# SparkIO_Thermal_Shield_-_No_Aux_ADC.net
KiCad netlist of a schematic drawn in Altium Designer
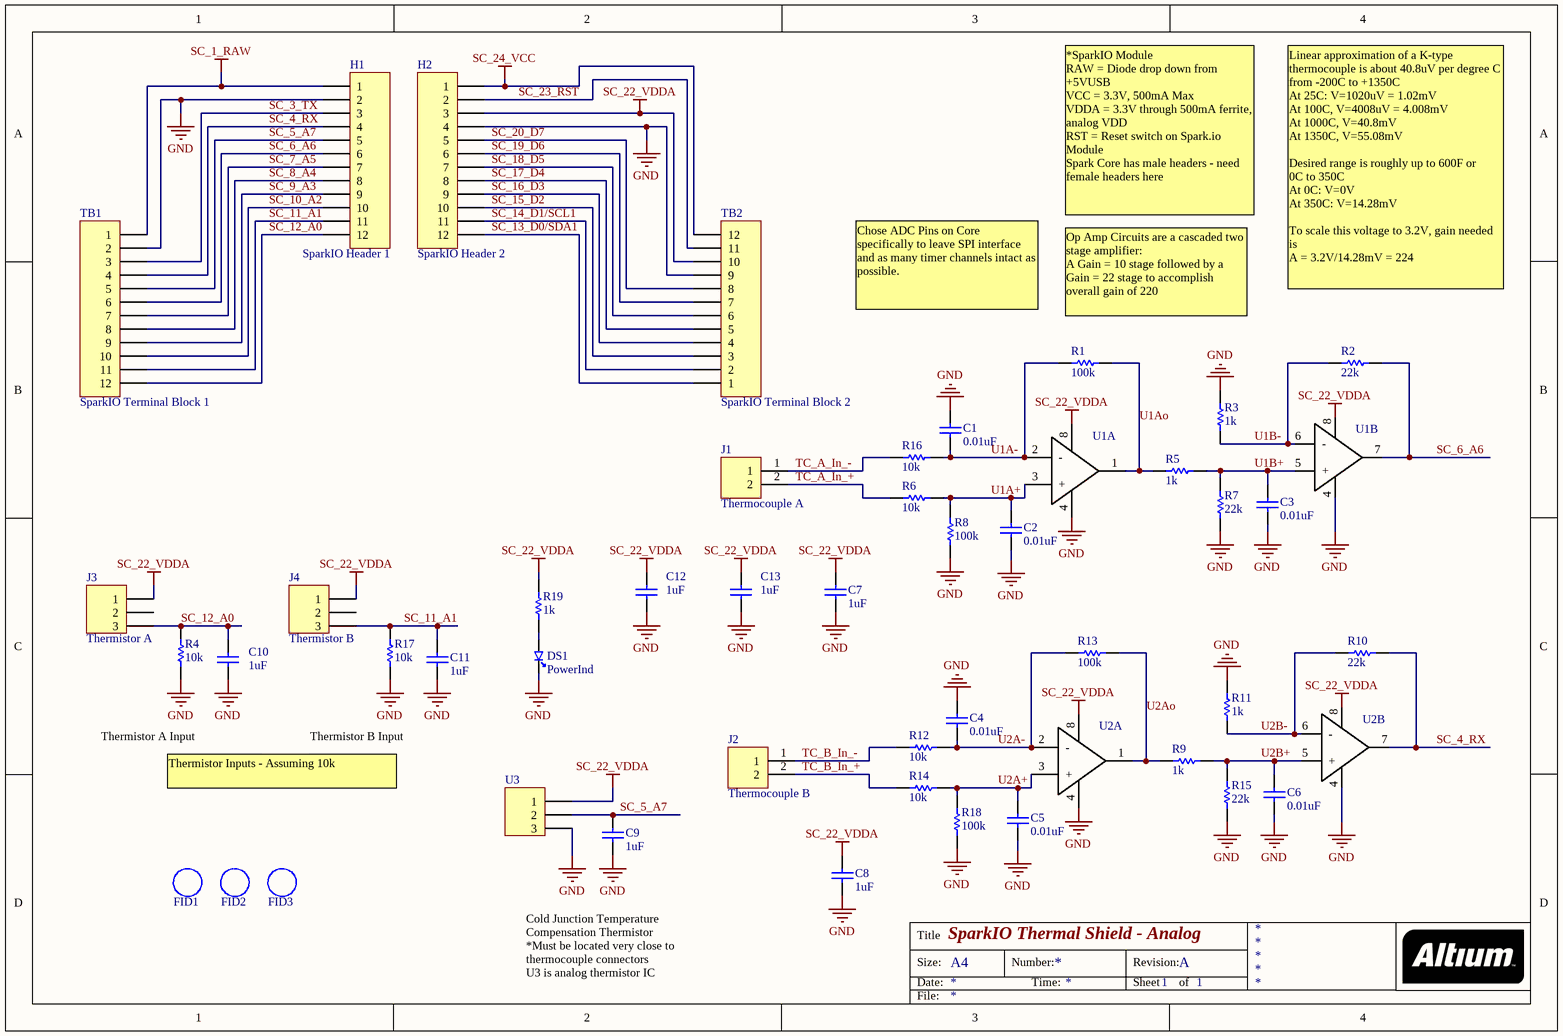
[diagram p0: SparkIO Thermal Shield - No Aux ADC.SchDoc]

(export (version "E")
  (design (tool "Eeschema 10.0.6"))
  (components
    (comp (ref "C1")
      (value "0.01uF")
      (footprint "0603 - NO SILK")
      (description "Capacitor")
      (fields
        (field (name "MANUFACTURER") "TDK Corporation")
        (field (name "MANUFACTURER PART NUMBER") "C1608X7R1E103K080AA")
      )
      (libsource (lib "MakerBot") (part "Capacitor"))
    )
    (comp (ref "C2")
      (value "0.01uF")
      (footprint "0603 - NO SILK")
      (description "Capacitor")
      (fields
        (field (name "MANUFACTURER") "TDK Corporation")
        (field (name "MANUFACTURER PART NUMBER") "C1608X7R1E103K080AA")
      )
      (libsource (lib "MakerBot") (part "Capacitor"))
    )
    (comp (ref "C3")
      (value "0.01uF")
      (footprint "0603 - NO SILK")
      (description "Capacitor")
      (fields
        (field (name "MANUFACTURER") "TDK Corporation")
        (field (name "MANUFACTURER PART NUMBER") "C1608X7R1E103K080AA")
      )
      (libsource (lib "MakerBot") (part "Capacitor"))
    )
    (comp (ref "C4")
      (value "0.01uF")
      (footprint "0603 - NO SILK")
      (description "Capacitor")
      (fields
        (field (name "MANUFACTURER") "TDK Corporation")
        (field (name "MANUFACTURER PART NUMBER") "C1608X7R1E103K080AA")
      )
      (libsource (lib "MakerBot") (part "Capacitor"))
    )
    (comp (ref "C5")
      (value "0.01uF")
      (footprint "0603 - NO SILK")
      (description "Capacitor")
      (fields
        (field (name "MANUFACTURER") "TDK Corporation")
        (field (name "MANUFACTURER PART NUMBER") "C1608X7R1E103K080AA")
      )
      (libsource (lib "MakerBot") (part "Capacitor"))
    )
    (comp (ref "C6")
      (value "0.01uF")
      (footprint "0603 - NO SILK")
      (description "Capacitor")
      (fields
        (field (name "MANUFACTURER") "TDK Corporation")
        (field (name "MANUFACTURER PART NUMBER") "C1608X7R1E103K080AA")
      )
      (libsource (lib "MakerBot") (part "Capacitor"))
    )
    (comp (ref "C7")
      (value "1uF")
      (footprint "0603 - NO SILK")
      (description "Capacitor")
      (fields
        (field (name "MANUFACTURER") "TDK Corporation")
        (field (name "MANUFACTURER PART NUMBER") "C1608X7R1C105K080AC")
      )
      (libsource (lib "MakerBot") (part "Capacitor"))
    )
    (comp (ref "C8")
      (value "1uF")
      (footprint "0603 - NO SILK")
      (description "Capacitor")
      (fields
        (field (name "MANUFACTURER") "TDK Corporation")
        (field (name "MANUFACTURER PART NUMBER") "C1608X7R1C105K080AC")
      )
      (libsource (lib "MakerBot") (part "Capacitor"))
    )
    (comp (ref "C9")
      (value "1uF")
      (footprint "0603 - NO SILK")
      (description "Capacitor")
      (fields
        (field (name "MANUFACTURER") "TDK Corporation")
        (field (name "MANUFACTURER PART NUMBER") "C1608X7R1C105K080AC")
      )
      (libsource (lib "MakerBot") (part "Capacitor"))
    )
    (comp (ref "C10")
      (value "1uF")
      (footprint "0603 - NO SILK")
      (description "Capacitor")
      (fields
        (field (name "MANUFACTURER") "TDK Corporation")
        (field (name "MANUFACTURER PART NUMBER") "C1608X7R1C105K080AC")
      )
      (libsource (lib "MakerBot") (part "Capacitor"))
    )
    (comp (ref "C11")
      (value "1uF")
      (footprint "0603 - NO SILK")
      (description "Capacitor")
      (fields
        (field (name "MANUFACTURER") "TDK Corporation")
        (field (name "MANUFACTURER PART NUMBER") "C1608X7R1C105K080AC")
      )
      (libsource (lib "MakerBot") (part "Capacitor"))
    )
    (comp (ref "C12")
      (value "1uF")
      (footprint "0603 - NO SILK")
      (description "Capacitor")
      (fields
        (field (name "MANUFACTURER") "TDK Corporation")
        (field (name "MANUFACTURER PART NUMBER") "C1608X7R1C105K080AC")
      )
      (libsource (lib "MakerBot") (part "Capacitor"))
    )
    (comp (ref "C13")
      (value "1uF")
      (footprint "0603 - NO SILK")
      (description "Capacitor")
      (fields
        (field (name "MANUFACTURER") "TDK Corporation")
        (field (name "MANUFACTURER PART NUMBER") "C1608X7R1C105K080AC")
      )
      (libsource (lib "MakerBot") (part "Capacitor"))
    )
    (comp (ref "DS1")
      (value "PowerInd")
      (footprint "LED0603 - Single")
      (description "LED small symbol")
      (fields
        (field (name "MANUFACTURER") "LiteOn")
        (field (name "MANUFACTURER PART NUMBER") "LTST-C190KGKT")
      )
      (libsource (lib "MakerBot") (part "LED Small"))
    )
    (comp (ref "FID1")
      (value "Fiducial")
      (footprint "Fiducial_40mil")
      (libsource (lib "MakerBot") (part "Fiducial_1"))
    )
    (comp (ref "FID2")
      (value "Fiducial")
      (footprint "Fiducial_40mil")
      (libsource (lib "MakerBot") (part "Fiducial_1"))
    )
    (comp (ref "FID3")
      (value "Fiducial")
      (footprint "Fiducial_40mil")
      (libsource (lib "MakerBot") (part "Fiducial_1"))
    )
    (comp (ref "H1")
      (value "SparkIO Header 1")
      (footprint "HDR1X12")
      (description "Header, 12-Pin")
      (fields
        (field (name "MANUFACTURER") "Sullins Interconnect")
        (field (name "MANUFACTURER PART NUMBER") "PPTC121LFBN-RC")
      )
      (libsource (lib "") (part "Header 12_1"))
    )
    (comp (ref "H2")
      (value "SparkIO Header 2")
      (footprint "HDR1X12")
      (description "Header, 12-Pin")
      (fields
        (field (name "MANUFACTURER") "Sullins Interconnect")
        (field (name "MANUFACTURER PART NUMBER") "PPTC121LFBN-RC")
      )
      (libsource (lib "Miscellaneous Connectors") (part "Header 12"))
    )
    (comp (ref "J1")
      (value "Thermocouple A")
      (footprint "PCC-SMP K Thermocouple")
      (description "Header .1\" 2 Pos")
      (fields (field (name "MANUFACTURER") "Omega") (field (name "MANUFACTURER PART NUMBER") "PCC-SMP-K"))
      (libsource (lib "MakerBot") (part "Header 2"))
    )
    (comp (ref "J2")
      (value "Thermocouple B")
      (footprint "PCC-SMP K Thermocouple")
      (description "Header .1\" 2 Pos")
      (fields (field (name "MANUFACTURER") "Omega") (field (name "MANUFACTURER PART NUMBER") "PCC-SMP-K"))
      (libsource (lib "MakerBot") (part "Header 2"))
    )
    (comp (ref "J3")
      (value "Thermistor A")
      (footprint "Audio Jack 2.5mm Mono")
      (description "Header .1\" 3 Pos")
      (fields (field (name "MANUFACTURER") "CUI Inc") (field (name "MANUFACTURER PART NUMBER") "MJ-2509N"))
      (libsource (lib "MakerBot") (part "Header 3"))
    )
    (comp (ref "J4")
      (value "Thermistor B")
      (footprint "Audio Jack 2.5mm Mono")
      (description "Header .1\" 3 Pos")
      (fields (field (name "MANUFACTURER") "CUI Inc") (field (name "MANUFACTURER PART NUMBER") "MJ-2509N"))
      (libsource (lib "MakerBot") (part "Header 3"))
    )
    (comp (ref "R1")
      (value "100k")
      (footprint "0603 - NO SILK")
      (description "Resistor")
      (fields (field (name "TOLERANCE") "1%") (field (name "POWER") "1/10W"))
      (libsource (lib "MakerBot") (part "Resistor"))
    )
    (comp (ref "R2")
      (value "22k")
      (footprint "0603 - NO SILK")
      (description "Resistor")
      (fields (field (name "TOLERANCE") "1%") (field (name "POWER") "1/10W"))
      (libsource (lib "MakerBot") (part "Resistor"))
    )
    (comp (ref "R3")
      (value "1k")
      (footprint "0603 - NO SILK")
      (description "Resistor")
      (fields (field (name "TOLERANCE") "1%") (field (name "POWER") "1/10W"))
      (libsource (lib "MakerBot") (part "Resistor"))
    )
    (comp (ref "R4")
      (value "10k")
      (footprint "0603 - NO SILK")
      (description "Resistor")
      (fields (field (name "TOLERANCE") "1%") (field (name "POWER") "1/10W"))
      (libsource (lib "MakerBot") (part "Resistor"))
    )
    (comp (ref "R5")
      (value "1k")
      (footprint "0603 - NO SILK")
      (description "Resistor")
      (fields (field (name "TOLERANCE") "1%") (field (name "POWER") "1/10W"))
      (libsource (lib "MakerBot") (part "Resistor"))
    )
    (comp (ref "R6")
      (value "10k")
      (footprint "0603 - NO SILK")
      (description "Resistor")
      (fields (field (name "TOLERANCE") "1%") (field (name "POWER") "1/10W"))
      (libsource (lib "MakerBot") (part "Resistor"))
    )
    (comp (ref "R7")
      (value "22k")
      (footprint "0603 - NO SILK")
      (description "Resistor")
      (fields (field (name "TOLERANCE") "1%") (field (name "POWER") "1/10W"))
      (libsource (lib "MakerBot") (part "Resistor"))
    )
    (comp (ref "R8")
      (value "100k")
      (footprint "0603 - NO SILK")
      (description "Resistor")
      (fields (field (name "TOLERANCE") "1%") (field (name "POWER") "1/10W"))
      (libsource (lib "MakerBot") (part "Resistor"))
    )
    (comp (ref "R9")
      (value "1k")
      (footprint "0603 - NO SILK")
      (description "Resistor")
      (fields (field (name "TOLERANCE") "1%") (field (name "POWER") "1/10W"))
      (libsource (lib "MakerBot") (part "Resistor"))
    )
    (comp (ref "R10")
      (value "22k")
      (footprint "0603 - NO SILK")
      (description "Resistor")
      (fields (field (name "TOLERANCE") "1%") (field (name "POWER") "1/10W"))
      (libsource (lib "MakerBot") (part "Resistor"))
    )
    (comp (ref "R11")
      (value "1k")
      (footprint "0603 - NO SILK")
      (description "Resistor")
      (fields (field (name "TOLERANCE") "1%") (field (name "POWER") "1/10W"))
      (libsource (lib "MakerBot") (part "Resistor"))
    )
    (comp (ref "R12")
      (value "10k")
      (footprint "0603 - NO SILK")
      (description "Resistor")
      (fields (field (name "TOLERANCE") "1%") (field (name "POWER") "1/10W"))
      (libsource (lib "MakerBot") (part "Resistor"))
    )
    (comp (ref "R13")
      (value "100k")
      (footprint "0603 - NO SILK")
      (description "Resistor")
      (fields (field (name "TOLERANCE") "1%") (field (name "POWER") "1/10W"))
      (libsource (lib "MakerBot") (part "Resistor"))
    )
    (comp (ref "R14")
      (value "10k")
      (footprint "0603 - NO SILK")
      (description "Resistor")
      (fields (field (name "TOLERANCE") "1%") (field (name "POWER") "1/10W"))
      (libsource (lib "MakerBot") (part "Resistor"))
    )
    (comp (ref "R15")
      (value "22k")
      (footprint "0603 - NO SILK")
      (description "Resistor")
      (fields (field (name "TOLERANCE") "1%") (field (name "POWER") "1/10W"))
      (libsource (lib "MakerBot") (part "Resistor"))
    )
    (comp (ref "R16")
      (value "10k")
      (footprint "0603 - NO SILK")
      (description "Resistor")
      (fields (field (name "TOLERANCE") "1%") (field (name "POWER") "1/10W"))
      (libsource (lib "MakerBot") (part "Resistor"))
    )
    (comp (ref "R17")
      (value "10k")
      (footprint "0603 - NO SILK")
      (description "Resistor")
      (fields (field (name "TOLERANCE") "1%") (field (name "POWER") "1/10W"))
      (libsource (lib "MakerBot") (part "Resistor"))
    )
    (comp (ref "R18")
      (value "100k")
      (footprint "0603 - NO SILK")
      (description "Resistor")
      (fields (field (name "TOLERANCE") "1%") (field (name "POWER") "1/10W"))
      (libsource (lib "MakerBot") (part "Resistor"))
    )
    (comp (ref "R19")
      (value "1k")
      (footprint "0603 - NO SILK")
      (description "Resistor")
      (fields (field (name "TOLERANCE") "1%") (field (name "POWER") "1/10W"))
      (libsource (lib "MakerBot") (part "Resistor"))
    )
    (comp (ref "TB1")
      (value "SparkIO Terminal Block 1")
      (footprint "Terminal Block 3.5mm x 12")
      (description "Header, 12-Pin")
      (fields
        (field (name "MANUFACTURER") "On Shore Technology")
        (field (name "MANUFACTURER PART NUMBER") "OSTTE120104")
      )
      (libsource (lib "Miscellaneous Connectors") (part "Header 12"))
    )
    (comp (ref "TB2")
      (value "SparkIO Terminal Block 2")
      (footprint "Terminal Block 3.5mm x 12")
      (description "Header, 12-Pin")
      (fields
        (field (name "MANUFACTURER") "On Shore Technology")
        (field (name "MANUFACTURER PART NUMBER") "OSTTE120104")
      )
      (libsource (lib "") (part "Header 12_2"))
    )
    (comp (ref "U1")
      (value "OPAMP dual")
      (footprint "SOIC8")
      (description "Dual Operational Amplifier")
      (fields
        (field (name "MANUFACTURER") "Texas Instruments")
        (field (name "MANUFACTURER PART NUMBER") "OPA2376AIDR")
      )
      (libsource (lib "MakerBot") (part "OPAMP dual"))
    )
    (comp (ref "U2")
      (value "OPAMP dual")
      (footprint "SOIC8")
      (description "Dual Operational Amplifier")
      (fields
        (field (name "MANUFACTURER") "Texas Instruments")
        (field (name "MANUFACTURER PART NUMBER") "OPA2376AIDR")
      )
      (libsource (lib "MakerBot") (part "OPAMP dual"))
    )
    (comp (ref "U3")
      (value "Header 3")
      (footprint "SOT23-3L")
      (description "Header .1\" 3 Pos")
      (fields
        (field (name "MANUFACTURER") "Microchip")
        (field (name "MANUFACTURER PART NUMBER") "TC1046VNBTR")
      )
      (libsource (lib "MakerBot") (part "Header 3"))
    )
  )
  (nets
    (net (code "1") (name "/SC_3_TX") (class "Default")
      (node (ref "H1") (pin "3") (pinfunction "3_3") (pintype "passive"))
      (node (ref "TB1") (pin "3") (pinfunction "3_3") (pintype "passive"))
    )
    (net (code "2") (name "/SC_4_RX") (class "Default")
      (node (ref "H1") (pin "4") (pinfunction "4_4") (pintype "passive"))
      (node (ref "R10") (pin "1") (pinfunction "1_1") (pintype "passive"))
      (node (ref "TB1") (pin "4") (pinfunction "4_4") (pintype "passive"))
      (node (ref "U2") (pin "7") (pinfunction "O_7") (pintype "passive"))
    )
    (net (code "3") (name "/SC_5_A7") (class "Default")
      (node (ref "C9") (pin "1") (pinfunction "1_1") (pintype "passive"))
      (node (ref "H1") (pin "5") (pinfunction "5_5") (pintype "passive"))
      (node (ref "TB1") (pin "5") (pinfunction "5_5") (pintype "passive"))
      (node (ref "U3") (pin "2") (pinfunction "2_2") (pintype "passive"))
    )
    (net (code "4") (name "/SC_6_A6") (class "Default")
      (node (ref "H1") (pin "6") (pinfunction "6_6") (pintype "passive"))
      (node (ref "R2") (pin "1") (pinfunction "1_1") (pintype "passive"))
      (node (ref "TB1") (pin "6") (pinfunction "6_6") (pintype "passive"))
      (node (ref "U1") (pin "7") (pinfunction "O_7") (pintype "passive"))
    )
    (net (code "5") (name "/SC_7_A5") (class "Default")
      (node (ref "H1") (pin "7") (pinfunction "7_7") (pintype "passive"))
      (node (ref "TB1") (pin "7") (pinfunction "7_7") (pintype "passive"))
    )
    (net (code "6") (name "/SC_8_A4") (class "Default")
      (node (ref "H1") (pin "8") (pinfunction "8_8") (pintype "passive"))
      (node (ref "TB1") (pin "8") (pinfunction "8_8") (pintype "passive"))
    )
    (net (code "7") (name "/SC_9_A3") (class "Default")
      (node (ref "H1") (pin "9") (pinfunction "9_9") (pintype "passive"))
      (node (ref "TB1") (pin "9") (pinfunction "9_9") (pintype "passive"))
    )
    (net (code "8") (name "/SC_10_A2") (class "Default")
      (node (ref "H1") (pin "10") (pinfunction "10_10") (pintype "passive"))
      (node (ref "TB1") (pin "10") (pinfunction "10_10") (pintype "passive"))
    )
    (net (code "9") (name "/SC_11_A1") (class "Default")
      (node (ref "C11") (pin "1") (pinfunction "1_1") (pintype "passive"))
      (node (ref "H1") (pin "11") (pinfunction "11_11") (pintype "passive"))
      (node (ref "J4") (pin "3") (pinfunction "3_3") (pintype "passive"))
      (node (ref "R17") (pin "1") (pinfunction "1_1") (pintype "passive"))
      (node (ref "TB1") (pin "11") (pinfunction "11_11") (pintype "passive"))
    )
    (net (code "10") (name "/SC_12_A0") (class "Default")
      (node (ref "C10") (pin "1") (pinfunction "1_1") (pintype "passive"))
      (node (ref "H1") (pin "12") (pinfunction "12_12") (pintype "passive"))
      (node (ref "J3") (pin "3") (pinfunction "3_3") (pintype "passive"))
      (node (ref "R4") (pin "1") (pinfunction "1_1") (pintype "passive"))
      (node (ref "TB1") (pin "12") (pinfunction "12_12") (pintype "passive"))
    )
    (net (code "11") (name "/SC_13_D0{slash}SDA1") (class "Default")
      (node (ref "H2") (pin "12") (pinfunction "12_12") (pintype "passive"))
      (node (ref "TB2") (pin "1") (pinfunction "1_1") (pintype "passive"))
    )
    (net (code "12") (name "/SC_14_D1{slash}SCL1") (class "Default")
      (node (ref "H2") (pin "11") (pinfunction "11_11") (pintype "passive"))
      (node (ref "TB2") (pin "2") (pinfunction "2_2") (pintype "passive"))
    )
    (net (code "13") (name "/SC_15_D2") (class "Default")
      (node (ref "H2") (pin "10") (pinfunction "10_10") (pintype "passive"))
      (node (ref "TB2") (pin "3") (pinfunction "3_3") (pintype "passive"))
    )
    (net (code "14") (name "/SC_16_D3") (class "Default")
      (node (ref "H2") (pin "9") (pinfunction "9_9") (pintype "passive"))
      (node (ref "TB2") (pin "4") (pinfunction "4_4") (pintype "passive"))
    )
    (net (code "15") (name "/SC_17_D4") (class "Default")
      (node (ref "H2") (pin "8") (pinfunction "8_8") (pintype "passive"))
      (node (ref "TB2") (pin "5") (pinfunction "5_5") (pintype "passive"))
    )
    (net (code "16") (name "/SC_18_D5") (class "Default")
      (node (ref "H2") (pin "7") (pinfunction "7_7") (pintype "passive"))
      (node (ref "TB2") (pin "6") (pinfunction "6_6") (pintype "passive"))
    )
    (net (code "17") (name "/SC_19_D6") (class "Default")
      (node (ref "H2") (pin "6") (pinfunction "6_6") (pintype "passive"))
      (node (ref "TB2") (pin "7") (pinfunction "7_7") (pintype "passive"))
    )
    (net (code "18") (name "/SC_20_D7") (class "Default")
      (node (ref "H2") (pin "5") (pinfunction "5_5") (pintype "passive"))
      (node (ref "TB2") (pin "8") (pinfunction "8_8") (pintype "passive"))
    )
    (net (code "19") (name "/SC_23_RST") (class "Default")
      (node (ref "H2") (pin "2") (pinfunction "2_2") (pintype "passive"))
      (node (ref "TB2") (pin "11") (pinfunction "11_11") (pintype "passive"))
    )
    (net (code "20") (name "/TC_A_In_+") (class "Default")
      (node (ref "J1") (pin "2") (pinfunction "2_2") (pintype "passive"))
      (node (ref "R6") (pin "2") (pinfunction "2_2") (pintype "passive"))
    )
    (net (code "21") (name "/TC_A_In_-") (class "Default")
      (node (ref "J1") (pin "1") (pinfunction "1_1") (pintype "passive"))
      (node (ref "R16") (pin "2") (pinfunction "2_2") (pintype "passive"))
    )
    (net (code "22") (name "/TC_B_In_+") (class "Default")
      (node (ref "J2") (pin "2") (pinfunction "2_2") (pintype "passive"))
      (node (ref "R14") (pin "2") (pinfunction "2_2") (pintype "passive"))
    )
    (net (code "23") (name "/TC_B_In_-") (class "Default")
      (node (ref "J2") (pin "1") (pinfunction "1_1") (pintype "passive"))
      (node (ref "R12") (pin "2") (pinfunction "2_2") (pintype "passive"))
    )
    (net (code "24") (name "/U1A+") (class "Default")
      (node (ref "C2") (pin "1") (pinfunction "1_1") (pintype "passive"))
      (node (ref "R6") (pin "1") (pinfunction "1_1") (pintype "passive"))
      (node (ref "R8") (pin "2") (pinfunction "2_2") (pintype "passive"))
      (node (ref "U1") (pin "3") (pinfunction "+_3") (pintype "passive"))
    )
    (net (code "25") (name "/U1A-") (class "Default")
      (node (ref "C1") (pin "2") (pinfunction "2_2") (pintype "passive"))
      (node (ref "R1") (pin "2") (pinfunction "2_2") (pintype "passive"))
      (node (ref "R16") (pin "1") (pinfunction "1_1") (pintype "passive"))
      (node (ref "U1") (pin "2") (pinfunction "-_2") (pintype "passive"))
    )
    (net (code "26") (name "/U1Ao") (class "Default")
      (node (ref "R1") (pin "1") (pinfunction "1_1") (pintype "passive"))
      (node (ref "R5") (pin "2") (pinfunction "2_2") (pintype "passive"))
      (node (ref "U1") (pin "1") (pinfunction "O_1") (pintype "passive"))
    )
    (net (code "27") (name "/U1B+") (class "Default")
      (node (ref "C3") (pin "1") (pinfunction "1_1") (pintype "passive"))
      (node (ref "R5") (pin "1") (pinfunction "1_1") (pintype "passive"))
      (node (ref "R7") (pin "2") (pinfunction "2_2") (pintype "passive"))
      (node (ref "U1") (pin "5") (pinfunction "+_5") (pintype "passive"))
    )
    (net (code "28") (name "/U1B-") (class "Default")
      (node (ref "R2") (pin "2") (pinfunction "2_2") (pintype "passive"))
      (node (ref "R3") (pin "2") (pinfunction "2_2") (pintype "passive"))
      (node (ref "U1") (pin "6") (pinfunction "-_6") (pintype "passive"))
    )
    (net (code "29") (name "/U2A+") (class "Default")
      (node (ref "C5") (pin "1") (pinfunction "1_1") (pintype "passive"))
      (node (ref "R14") (pin "1") (pinfunction "1_1") (pintype "passive"))
      (node (ref "R18") (pin "2") (pinfunction "2_2") (pintype "passive"))
      (node (ref "U2") (pin "3") (pinfunction "+_3") (pintype "passive"))
    )
    (net (code "30") (name "/U2A-") (class "Default")
      (node (ref "C4") (pin "2") (pinfunction "2_2") (pintype "passive"))
      (node (ref "R12") (pin "1") (pinfunction "1_1") (pintype "passive"))
      (node (ref "R13") (pin "2") (pinfunction "2_2") (pintype "passive"))
      (node (ref "U2") (pin "2") (pinfunction "-_2") (pintype "passive"))
    )
    (net (code "31") (name "/U2Ao") (class "Default")
      (node (ref "R13") (pin "1") (pinfunction "1_1") (pintype "passive"))
      (node (ref "R9") (pin "2") (pinfunction "2_2") (pintype "passive"))
      (node (ref "U2") (pin "1") (pinfunction "O_1") (pintype "passive"))
    )
    (net (code "32") (name "/U2B+") (class "Default")
      (node (ref "C6") (pin "1") (pinfunction "1_1") (pintype "passive"))
      (node (ref "R15") (pin "2") (pinfunction "2_2") (pintype "passive"))
      (node (ref "R9") (pin "1") (pinfunction "1_1") (pintype "passive"))
      (node (ref "U2") (pin "5") (pinfunction "+_5") (pintype "passive"))
    )
    (net (code "33") (name "/U2B-") (class "Default")
      (node (ref "R10") (pin "2") (pinfunction "2_2") (pintype "passive"))
      (node (ref "R11") (pin "2") (pinfunction "2_2") (pintype "passive"))
      (node (ref "U2") (pin "6") (pinfunction "-_6") (pintype "passive"))
    )
    (net (code "34") (name "GND") (class "Default")
      (node (ref "C1") (pin "1") (pinfunction "1_1") (pintype "passive"))
      (node (ref "C10") (pin "2") (pinfunction "2_2") (pintype "passive"))
      (node (ref "C11") (pin "2") (pinfunction "2_2") (pintype "passive"))
      (node (ref "C12") (pin "2") (pinfunction "2_2") (pintype "passive"))
      (node (ref "C13") (pin "2") (pinfunction "2_2") (pintype "passive"))
      (node (ref "C2") (pin "2") (pinfunction "2_2") (pintype "passive"))
      (node (ref "C3") (pin "2") (pinfunction "2_2") (pintype "passive"))
      (node (ref "C4") (pin "1") (pinfunction "1_1") (pintype "passive"))
      (node (ref "C5") (pin "2") (pinfunction "2_2") (pintype "passive"))
      (node (ref "C6") (pin "2") (pinfunction "2_2") (pintype "passive"))
      (node (ref "C7") (pin "2") (pinfunction "2_2") (pintype "passive"))
      (node (ref "C8") (pin "2") (pinfunction "2_2") (pintype "passive"))
      (node (ref "C9") (pin "2") (pinfunction "2_2") (pintype "passive"))
      (node (ref "DS1") (pin "2") (pinfunction "K_2") (pintype "passive"))
      (node (ref "H1") (pin "2") (pinfunction "2_2") (pintype "passive"))
      (node (ref "H2") (pin "4") (pinfunction "4_4") (pintype "passive"))
      (node (ref "R11") (pin "1") (pinfunction "1_1") (pintype "passive"))
      (node (ref "R15") (pin "1") (pinfunction "1_1") (pintype "passive"))
      (node (ref "R17") (pin "2") (pinfunction "2_2") (pintype "passive"))
      (node (ref "R18") (pin "1") (pinfunction "1_1") (pintype "passive"))
      (node (ref "R3") (pin "1") (pinfunction "1_1") (pintype "passive"))
      (node (ref "R4") (pin "2") (pinfunction "2_2") (pintype "passive"))
      (node (ref "R7") (pin "1") (pinfunction "1_1") (pintype "passive"))
      (node (ref "R8") (pin "1") (pinfunction "1_1") (pintype "passive"))
      (node (ref "TB1") (pin "2") (pinfunction "2_2") (pintype "passive"))
      (node (ref "TB2") (pin "9") (pinfunction "9_9") (pintype "passive"))
      (node (ref "U1") (pin "4") (pinfunction "V-_4") (pintype "power_in"))
      (node (ref "U2") (pin "4") (pinfunction "V-_4") (pintype "power_in"))
      (node (ref "U3") (pin "3") (pinfunction "3_3") (pintype "passive"))
    )
    (net (code "35") (name "Net-(DS1-A)") (class "Default")
      (node (ref "DS1") (pin "1") (pinfunction "A_1") (pintype "passive"))
      (node (ref "R19") (pin "2") (pinfunction "2_2") (pintype "passive"))
    )
    (net (code "36") (name "SC_1_RAW") (class "Default")
      (node (ref "H1") (pin "1") (pinfunction "1_1") (pintype "passive"))
      (node (ref "TB1") (pin "1") (pinfunction "1_1") (pintype "passive"))
    )
    (net (code "37") (name "SC_22_VDDA") (class "Default")
      (node (ref "C12") (pin "1") (pinfunction "1_1") (pintype "passive"))
      (node (ref "C13") (pin "1") (pinfunction "1_1") (pintype "passive"))
      (node (ref "C7") (pin "1") (pinfunction "1_1") (pintype "passive"))
      (node (ref "C8") (pin "1") (pinfunction "1_1") (pintype "passive"))
      (node (ref "H2") (pin "3") (pinfunction "3_3") (pintype "passive"))
      (node (ref "J3") (pin "1") (pinfunction "1_1") (pintype "passive"))
      (node (ref "J4") (pin "1") (pinfunction "1_1") (pintype "passive"))
      (node (ref "R19") (pin "1") (pinfunction "1_1") (pintype "passive"))
      (node (ref "TB2") (pin "10") (pinfunction "10_10") (pintype "passive"))
      (node (ref "U1") (pin "8") (pinfunction "V+_8") (pintype "power_in"))
      (node (ref "U2") (pin "8") (pinfunction "V+_8") (pintype "power_in"))
      (node (ref "U3") (pin "1") (pinfunction "1_1") (pintype "passive"))
    )
    (net (code "38") (name "SC_24_VCC") (class "Default")
      (node (ref "H2") (pin "1") (pinfunction "1_1") (pintype "passive"))
      (node (ref "TB2") (pin "12") (pinfunction "12_12") (pintype "passive"))
    )
    (net (code "39") (name "unconnected-(J3-Pad2)") (class "Default")
      (node (ref "J3") (pin "2") (pinfunction "2_2") (pintype "passive"))
    )
    (net (code "40") (name "unconnected-(J4-Pad2)") (class "Default")
      (node (ref "J4") (pin "2") (pinfunction "2_2") (pintype "passive"))
    )
  )
)
